# uradmonitor_D.net
KiCad netlist of a schematic drawn in EAGLE
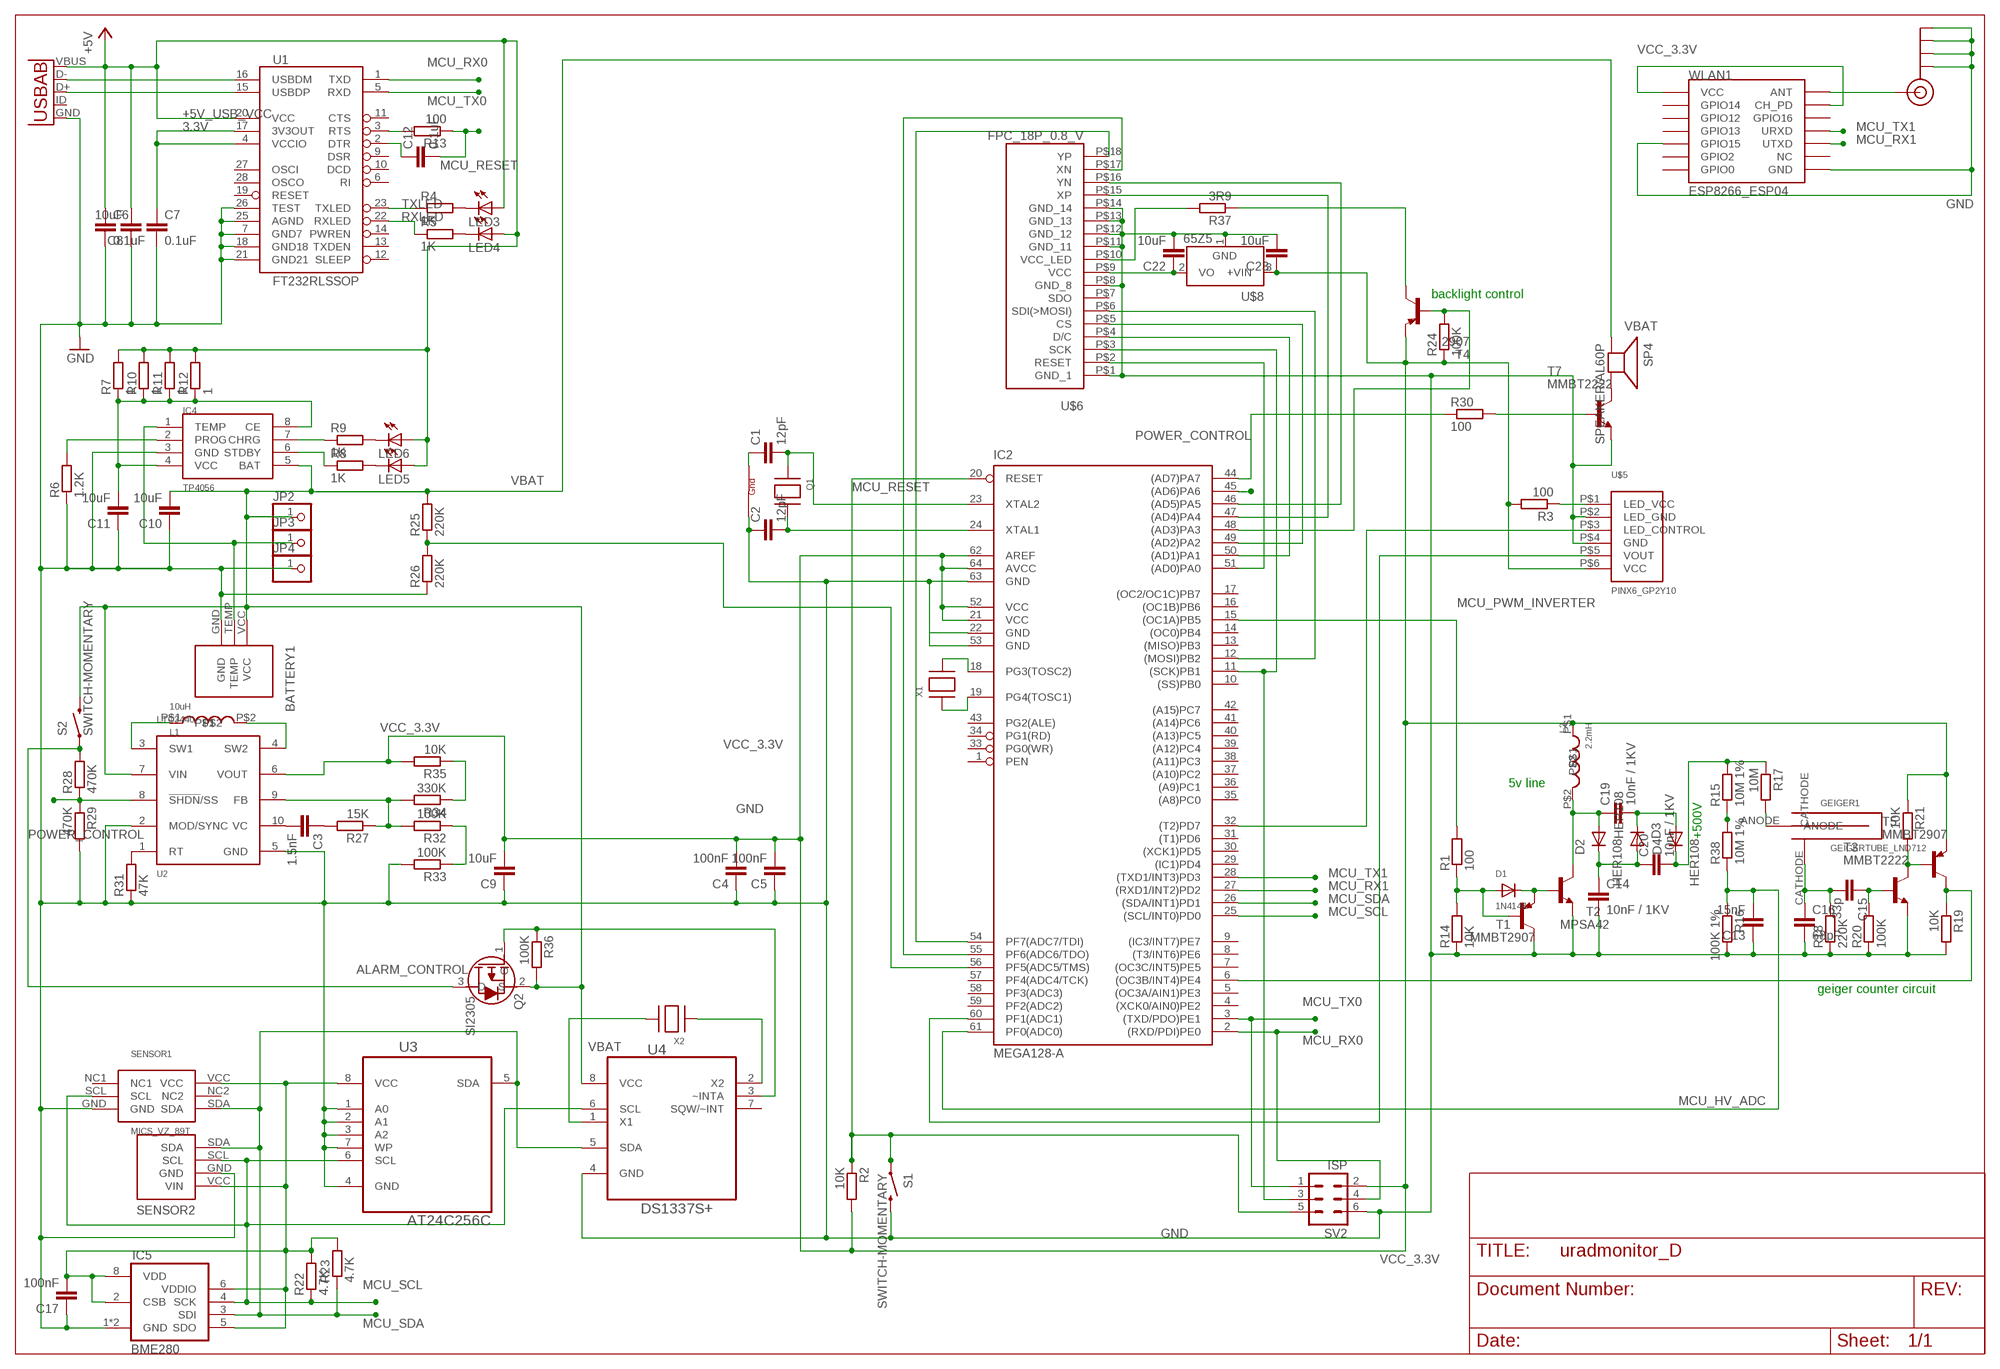
[diagram p0: schematic, sheet 1]

(export (version "E")
  (design (tool "Eeschema 10.0.6"))
  (components
    (comp (ref "BATTERY1")
      (value "BAT-CASIO-NP40BATTERY")
      (footprint "eagle-import:BAT-CASIO-NP40")
      (libsource (lib "eagle-import") (part "BAT-CASIO-NP40BATTERY"))
    )
    (comp (ref "C1")
      (value "12pF")
      (footprint "eagle-import:C0805K")
      (libsource (lib "eagle-import") (part "C-EUC0805K"))
    )
    (comp (ref "C2")
      (value "12pF")
      (footprint "eagle-import:C0805K")
      (libsource (lib "eagle-import") (part "C-EUC0805K"))
    )
    (comp (ref "C3")
      (value "1.5nF")
      (footprint "eagle-import:C0805K")
      (libsource (lib "eagle-import") (part "C-EUC0805K"))
    )
    (comp (ref "C4")
      (value "100nF")
      (footprint "eagle-import:C0805K")
      (libsource (lib "eagle-import") (part "C-EUC0805K"))
    )
    (comp (ref "C5")
      (value "100nF")
      (footprint "eagle-import:C0805K")
      (libsource (lib "eagle-import") (part "C-EUC0805K"))
    )
    (comp (ref "C6")
      (value "0.1uF")
      (footprint "eagle-import:0805")
      (libsource (lib "eagle-import") (part "CAP0805"))
    )
    (comp (ref "C7")
      (value "0.1uF")
      (footprint "eagle-import:0805")
      (libsource (lib "eagle-import") (part "CAP0805"))
    )
    (comp (ref "C8")
      (value "10uF")
      (footprint "eagle-import:C0805K")
      (libsource (lib "eagle-import") (part "C-EUC0805K"))
    )
    (comp (ref "C9")
      (value "10uF")
      (footprint "eagle-import:C0805K")
      (libsource (lib "eagle-import") (part "C-EUC0805K"))
    )
    (comp (ref "C10")
      (value "10uF")
      (footprint "eagle-import:C0805K")
      (libsource (lib "eagle-import") (part "C-EUC0805K"))
    )
    (comp (ref "C11")
      (value "10uF")
      (footprint "eagle-import:C0805K")
      (libsource (lib "eagle-import") (part "C-EUC0805K"))
    )
    (comp (ref "C12")
      (value "0.1uF")
      (footprint "eagle-import:0805")
      (libsource (lib "eagle-import") (part "CAP0805"))
    )
    (comp (ref "C13")
      (value "15nF")
      (footprint "eagle-import:C0805K")
      (libsource (lib "eagle-import") (part "C-EUC0805K"))
    )
    (comp (ref "C14")
      (value "10nF / 1KV")
      (footprint "eagle-import:C1206K")
      (libsource (lib "eagle-import") (part "C-EUC1206K"))
    )
    (comp (ref "C15")
      (value "33p")
      (footprint "eagle-import:C0805K")
      (libsource (lib "eagle-import") (part "C-EUC0805K"))
    )
    (comp (ref "C16")
      (value "68pF")
      (footprint "eagle-import:C0805K")
      (libsource (lib "eagle-import") (part "C-EUC0805K"))
    )
    (comp (ref "C17")
      (value "100nF")
      (footprint "eagle-import:C0805K")
      (libsource (lib "eagle-import") (part "C-EUC0805K"))
    )
    (comp (ref "C19")
      (value "10nF / 1KV")
      (footprint "eagle-import:C1206K")
      (libsource (lib "eagle-import") (part "C-EUC1206K"))
    )
    (comp (ref "C20")
      (value "10nF / 1KV")
      (footprint "eagle-import:C1206K")
      (libsource (lib "eagle-import") (part "C-EUC1206K"))
    )
    (comp (ref "C22")
      (value "10uF")
      (footprint "eagle-import:C0805")
      (libsource (lib "eagle-import") (part "resistor_C-EUC0805"))
    )
    (comp (ref "C23")
      (value "10uF")
      (footprint "eagle-import:C0805")
      (libsource (lib "eagle-import") (part "resistor_C-EUC0805"))
    )
    (comp (ref "D1")
      (value "1N4148")
      (footprint "eagle-import:SOD-323F")
      (libsource (lib "eagle-import") (part "DIODESOD-323F"))
    )
    (comp (ref "D2")
      (value "HER108")
      (footprint "eagle-import:DO-214AC")
      (libsource (lib "eagle-import") (part "DIODE-DO-214AC"))
    )
    (comp (ref "D3")
      (value "HER108")
      (footprint "eagle-import:DO-214AC")
      (libsource (lib "eagle-import") (part "DIODE-DO-214AC"))
    )
    (comp (ref "D4")
      (value "HER108")
      (footprint "eagle-import:DO-214AC")
      (libsource (lib "eagle-import") (part "DIODE-DO-214AC"))
    )
    (comp (ref "GEIGER1")
      (value "GEIGERTUBE_LND712")
      (footprint "eagle-import:GEIGERTUBE_LND712")
      (libsource (lib "eagle-import") (part "GEIGERTUBE_LND712"))
    )
    (comp (ref "IC2")
      (value "MEGA128-A")
      (footprint "eagle-import:TQFP64")
      (fields (field (name "MPN") "ATMEGA128-16AU"))
      (libsource (lib "eagle-import") (part "MEGA128-A"))
    )
    (comp (ref "IC4")
      (value "TP4056")
      (footprint "eagle-import:TP4056")
      (libsource (lib "eagle-import") (part "TP4056"))
    )
    (comp (ref "IC5")
      (value "BME280")
      (footprint "eagle-import:BME280")
      (libsource (lib "eagle-import") (part "BME280"))
    )
    (comp (ref "J$1")
      (value "SMA_EDGE")
      (footprint "eagle-import:SMA-EDGE")
      (libsource (lib "eagle-import") (part "SMA_EDGE"))
    )
    (comp (ref "JP2")
      (value "PINHD-1X1CB")
      (footprint "eagle-import:1X01-CLEANBIG")
      (libsource (lib "eagle-import") (part "PINHD-1X1CB"))
    )
    (comp (ref "JP3")
      (value "PINHD-1X1CB")
      (footprint "eagle-import:1X01-CLEANBIG")
      (libsource (lib "eagle-import") (part "PINHD-1X1CB"))
    )
    (comp (ref "JP4")
      (value "PINHD-1X1CB")
      (footprint "eagle-import:1X01-CLEANBIG")
      (libsource (lib "eagle-import") (part "PINHD-1X1CB"))
    )
    (comp (ref "L1")
      (value "10uH")
      (footprint "eagle-import:DO1608")
      (libsource (lib "eagle-import") (part "INDUCTOR"))
    )
    (comp (ref "L2")
      (value "2.2mH")
      (footprint "eagle-import:DO1608")
      (libsource (lib "eagle-import") (part "INDUCTOR"))
    )
    (comp (ref "LED3")
      (value "LEDCHIP-LED0805")
      (footprint "eagle-import:CHIP-LED0805")
      (libsource (lib "eagle-import") (part "LEDCHIP-LED0805"))
    )
    (comp (ref "LED4")
      (value "LEDCHIP-LED0805")
      (footprint "eagle-import:CHIP-LED0805")
      (libsource (lib "eagle-import") (part "LEDCHIP-LED0805"))
    )
    (comp (ref "LED5")
      (value "LED3MM")
      (footprint "eagle-import:LED3MM")
      (libsource (lib "eagle-import") (part "LED3MM"))
    )
    (comp (ref "LED6")
      (value "LED3MM")
      (footprint "eagle-import:LED3MM")
      (libsource (lib "eagle-import") (part "LED3MM"))
    )
    (comp (ref "Q1")
      (value "XTAL-4-3225")
      (footprint "eagle-import:NX3225")
      (libsource (lib "eagle-import") (part "XTAL-4-3225"))
    )
    (comp (ref "Q2")
      (value "SI2305")
      (footprint "eagle-import:SOT23")
      (libsource (lib "eagle-import") (part "SI2305"))
    )
    (comp (ref "R1")
      (value "100")
      (footprint "eagle-import:R0805")
      (libsource (lib "eagle-import") (part "resistor_R-EU_R0805"))
    )
    (comp (ref "R2")
      (value "10K")
      (footprint "eagle-import:R0805")
      (libsource (lib "eagle-import") (part "R-EU_R0805"))
    )
    (comp (ref "R3")
      (value "100")
      (footprint "eagle-import:R0805")
      (libsource (lib "eagle-import") (part "resistor_R-EU_R0805"))
    )
    (comp (ref "R4")
      (value "1K")
      (footprint "eagle-import:R0805")
      (libsource (lib "eagle-import") (part "R-EU_R0805"))
    )
    (comp (ref "R5")
      (value "1K")
      (footprint "eagle-import:R0805")
      (libsource (lib "eagle-import") (part "R-EU_R0805"))
    )
    (comp (ref "R6")
      (value "1.2K")
      (footprint "eagle-import:R0805")
      (libsource (lib "eagle-import") (part "R-EU_R0805"))
    )
    (comp (ref "R7")
      (value "1")
      (footprint "eagle-import:R0805")
      (libsource (lib "eagle-import") (part "R-EU_R0805"))
    )
    (comp (ref "R8")
      (value "1K")
      (footprint "eagle-import:R0805")
      (libsource (lib "eagle-import") (part "R-EU_R0805"))
    )
    (comp (ref "R9")
      (value "1K")
      (footprint "eagle-import:R0805")
      (libsource (lib "eagle-import") (part "R-EU_R0805"))
    )
    (comp (ref "R10")
      (value "1")
      (footprint "eagle-import:R0805")
      (libsource (lib "eagle-import") (part "R-EU_R0805"))
    )
    (comp (ref "R11")
      (value "1")
      (footprint "eagle-import:R0805")
      (libsource (lib "eagle-import") (part "R-EU_R0805"))
    )
    (comp (ref "R12")
      (value "1")
      (footprint "eagle-import:R0805")
      (libsource (lib "eagle-import") (part "R-EU_R0805"))
    )
    (comp (ref "R13")
      (value "100")
      (footprint "eagle-import:R0805")
      (libsource (lib "eagle-import") (part "R-EU_R0805"))
    )
    (comp (ref "R14")
      (value "10K")
      (footprint "eagle-import:R0805")
      (libsource (lib "eagle-import") (part "resistor_R-EU_R0805"))
    )
    (comp (ref "R15")
      (value "10M 1%")
      (footprint "eagle-import:0204_7")
      (libsource (lib "eagle-import") (part "R-EU_0204/7"))
    )
    (comp (ref "R16")
      (value "100K 1%")
      (footprint "eagle-import:R0805")
      (libsource (lib "eagle-import") (part "R-EU_R0805"))
    )
    (comp (ref "R17")
      (value "10M")
      (footprint "eagle-import:0204_7")
      (libsource (lib "eagle-import") (part "R-EU_0204/7"))
    )
    (comp (ref "R18")
      (value "220K")
      (footprint "eagle-import:0204_7")
      (libsource (lib "eagle-import") (part "R-EU_0204/7"))
    )
    (comp (ref "R19")
      (value "10K")
      (footprint "eagle-import:R0805")
      (libsource (lib "eagle-import") (part "R-EU_R0805"))
    )
    (comp (ref "R20")
      (value "100K")
      (footprint "eagle-import:R0805")
      (libsource (lib "eagle-import") (part "R-EU_R0805"))
    )
    (comp (ref "R21")
      (value "10K")
      (footprint "eagle-import:R0805")
      (libsource (lib "eagle-import") (part "R-EU_R0805"))
    )
    (comp (ref "R22")
      (value "4.7K")
      (footprint "eagle-import:R0805")
      (libsource (lib "eagle-import") (part "R-EU_R0805"))
    )
    (comp (ref "R23")
      (value "4.7K")
      (footprint "eagle-import:R0805")
      (libsource (lib "eagle-import") (part "R-EU_R0805"))
    )
    (comp (ref "R24")
      (value "100K")
      (footprint "eagle-import:R0805")
      (libsource (lib "eagle-import") (part "resistor_R-EU_R0805"))
    )
    (comp (ref "R25")
      (value "220K")
      (footprint "eagle-import:R0805")
      (libsource (lib "eagle-import") (part "R-EU_R0805"))
    )
    (comp (ref "R26")
      (value "220K")
      (footprint "eagle-import:R0805")
      (libsource (lib "eagle-import") (part "R-EU_R0805"))
    )
    (comp (ref "R27")
      (value "15K")
      (footprint "eagle-import:R0805")
      (libsource (lib "eagle-import") (part "R-EU_R0805"))
    )
    (comp (ref "R28")
      (value "470K")
      (footprint "eagle-import:R0805")
      (libsource (lib "eagle-import") (part "R-EU_R0805"))
    )
    (comp (ref "R29")
      (value "470K")
      (footprint "eagle-import:R0805")
      (libsource (lib "eagle-import") (part "R-EU_R0805"))
    )
    (comp (ref "R30")
      (value "100")
      (footprint "eagle-import:R0805")
      (libsource (lib "eagle-import") (part "R-EU_R0805"))
    )
    (comp (ref "R31")
      (value "47K")
      (footprint "eagle-import:R0805")
      (libsource (lib "eagle-import") (part "R-EU_R0805"))
    )
    (comp (ref "R32")
      (value "100K")
      (footprint "eagle-import:R0805")
      (libsource (lib "eagle-import") (part "R-EU_R0805"))
    )
    (comp (ref "R33")
      (value "100K")
      (footprint "eagle-import:R0805")
      (libsource (lib "eagle-import") (part "R-EU_R0805"))
    )
    (comp (ref "R34")
      (value "330K")
      (footprint "eagle-import:R0805")
      (libsource (lib "eagle-import") (part "R-EU_R0805"))
    )
    (comp (ref "R35")
      (value "10K")
      (footprint "eagle-import:R0805")
      (libsource (lib "eagle-import") (part "R-EU_R0805"))
    )
    (comp (ref "R36")
      (value "100K")
      (footprint "eagle-import:R0805")
      (libsource (lib "eagle-import") (part "R-EU_R0805"))
    )
    (comp (ref "R37")
      (value "3R9")
      (footprint "eagle-import:R0805")
      (libsource (lib "eagle-import") (part "resistor_R-EU_R0805"))
    )
    (comp (ref "R38")
      (value "10M 1%")
      (footprint "eagle-import:0204_7")
      (libsource (lib "eagle-import") (part "R-EU_0204/7"))
    )
    (comp (ref "S1")
      (value "SWITCH-MOMENTARY")
      (footprint "eagle-import:TACTILE-SWITCH-1101NE")
      (libsource (lib "eagle-import") (part "SWITCH-MOMENTARY-2-SMD-1101NE"))
    )
    (comp (ref "S2")
      (value "SWITCH-MOMENTARY")
      (footprint "eagle-import:TACTILE-PTH-SIDEEZ")
      (libsource (lib "eagle-import") (part "SWITCH-MOMENTARY-2SIDE_EZ"))
    )
    (comp (ref "SENSOR1")
      (value "MICS_VZ_89T")
      (footprint "eagle-import:MICS_VZ_89T")
      (libsource (lib "eagle-import") (part "MICS_VZ_89T"))
    )
    (comp (ref "SENSOR2")
      (value "BMP180")
      (footprint "eagle-import:SENSOR_GY68")
      (libsource (lib "eagle-import") (part "SENSOR_GY68GY-86DIP"))
    )
    (comp (ref "SP4")
      (value "SPEAKER/AL60P")
      (footprint "eagle-import:AL60P")
      (libsource (lib "eagle-import") (part "SPEAKER/AL60P"))
    )
    (comp (ref "SV2")
      (value "ISP")
      (footprint "eagle-import:MA03-2")
      (libsource (lib "eagle-import") (part "MA03-2"))
    )
    (comp (ref "T1")
      (value "MMBT2907")
      (footprint "eagle-import:SOT23-BEC")
      (libsource (lib "eagle-import") (part "-PNP-SOT23-BECMMBT2907ALT1"))
    )
    (comp (ref "T2")
      (value "MPSA42")
      (footprint "eagle-import:SOT23-BEC")
      (libsource (lib "eagle-import") (part "transistor-neu-to92_-NPN-SOT23-BECMMBTA42LT1"))
    )
    (comp (ref "T3")
      (value "MMBT2222")
      (footprint "eagle-import:SOT23-BEC")
      (libsource (lib "eagle-import") (part "transistor-neu-to92_-NPN-SOT23-BECMMBT2222ALT1"))
    )
    (comp (ref "T4")
      (value "2907")
      (footprint "eagle-import:SOT23-BEC")
      (libsource (lib "eagle-import") (part "-PNP-SOT23-BECMMBT2907ALT1"))
    )
    (comp (ref "T5")
      (value "MMBT2907")
      (footprint "eagle-import:SOT23-BEC")
      (libsource (lib "eagle-import") (part "-PNP-SOT23-BECMMBT2907ALT1"))
    )
    (comp (ref "T7")
      (value "MMBT2222")
      (footprint "eagle-import:SOT23-BEC")
      (libsource (lib "eagle-import") (part "-NPN-SOT23-BECMMBT2222ALT1"))
    )
    (comp (ref "U$2")
      (value "USB_AB")
      (footprint "eagle-import:USB-AB-MICRO-SMD")
      (libsource (lib "eagle-import") (part "USB_AB"))
    )
    (comp (ref "U$5")
      (value "PINX6_GP2Y10")
      (footprint "eagle-import:PINX6_GP2Y10")
      (libsource (lib "eagle-import") (part "PINX6_GP2Y10"))
    )
    (comp (ref "U$6")
      (value "FPC_18P_0.8_V")
      (footprint "eagle-import:FPC_18P_0.8_V")
      (libsource (lib "eagle-import") (part "FPC_18P_0.8_V"))
    )
    (comp (ref "U$8")
      (value "65Z5")
      (footprint "eagle-import:SOT23")
      (libsource (lib "eagle-import") (part "65Z5"))
    )
    (comp (ref "U1")
      (value "FT232RLSSOP")
      (footprint "eagle-import:SSOP28DB")
      (libsource (lib "eagle-import") (part "FT232RLSSOP"))
    )
    (comp (ref "U2")
      (value "LTC3440")
      (footprint "eagle-import:MSOP-10")
      (libsource (lib "eagle-import") (part "LTC3440"))
    )
    (comp (ref "U3")
      (value "AT24C256C")
      (footprint "eagle-import:SOIC127P600X175-8N")
      (fields (field (name "MPN") "AT24C512BN-SH25-B"))
      (libsource (lib "eagle-import") (part "AT24C512BN-SH25-B"))
    )
    (comp (ref "U4")
      (value "DS1337S+")
      (footprint "eagle-import:SOIC127P600X175-8N")
      (libsource (lib "eagle-import") (part "DS1337S+"))
    )
    (comp (ref "WLAN1")
      (value "ESP8266_ESP04")
      (footprint "eagle-import:ESP8266_ESP04")
      (libsource (lib "eagle-import") (part "ESP8266_ESP04"))
    )
    (comp (ref "X1")
      (value "XTAL-3.2X1.5")
      (footprint "eagle-import:XTAL3215")
      (libsource (lib "eagle-import") (part "XTAL-3.2X1.5"))
    )
    (comp (ref "X2")
      (value "XTAL-3.2X1.5")
      (footprint "eagle-import:XTAL3215")
      (libsource (lib "eagle-import") (part "XTAL-3.2X1.5"))
    )
  )
  (nets
    (net (code "1") (name "+5V") (class "Default")
      (node (ref "C6") (pin "1") (pinfunction "1_1") (pintype "passive"))
      (node (ref "C8") (pin "2") (pinfunction "2_2") (pintype "passive"))
      (node (ref "LED3") (pin "A") (pinfunction "A_A") (pintype "passive"))
      (node (ref "LED4") (pin "A") (pinfunction "A_A") (pintype "passive"))
      (node (ref "LED5") (pin "A") (pinfunction "A_A") (pintype "passive"))
      (node (ref "LED6") (pin "A") (pinfunction "A_A") (pintype "passive"))
      (node (ref "R10") (pin "2") (pinfunction "2_2") (pintype "passive"))
      (node (ref "R11") (pin "2") (pinfunction "2_2") (pintype "passive"))
      (node (ref "R12") (pin "2") (pinfunction "2_2") (pintype "passive"))
      (node (ref "R7") (pin "2") (pinfunction "2_2") (pintype "passive"))
      (node (ref "U$2") (pin "VBUS") (pinfunction "VBUS_VBUS") (pintype "bidirectional"))
      (node (ref "U1") (pin "20") (pinfunction "VCC_20") (pintype "power_in"))
    )
    (net (code "2") (name "/3.3V") (class "Default")
      (node (ref "C7") (pin "1") (pinfunction "1_1") (pintype "passive"))
      (node (ref "U1") (pin "17") (pinfunction "3V3OUT_17") (pintype "output"))
      (node (ref "U1") (pin "4") (pinfunction "VCCIO_4") (pintype "power_in"))
    )
    (net (code "3") (name "/ALARM_CONTROL") (class "Default")
      (node (ref "Q2") (pin "3") (pinfunction "D_3") (pintype "bidirectional"))
      (node (ref "R28") (pin "2") (pinfunction "2_2") (pintype "passive"))
      (node (ref "S2") (pin "1") (pinfunction "1_1") (pintype "passive"))
    )
    (net (code "4") (name "/MCU_HV_ADC") (class "Default")
      (node (ref "C13") (pin "2") (pinfunction "2_2") (pintype "passive"))
      (node (ref "IC2") (pin "61") (pinfunction "PF0(ADC0)_61") (pintype "input"))
      (node (ref "R16") (pin "1") (pinfunction "1_1") (pintype "passive"))
      (node (ref "R38") (pin "1") (pinfunction "1_1") (pintype "passive"))
    )
    (net (code "5") (name "/MCU_PWM_INVERTER") (class "Default")
      (node (ref "IC2") (pin "15") (pinfunction "(OC1A)PB5_15") (pintype "bidirectional"))
      (node (ref "R1") (pin "2") (pinfunction "2_2") (pintype "passive"))
    )
    (net (code "6") (name "/MCU_RESET") (class "Default")
      (node (ref "C12") (pin "2") (pinfunction "2_2") (pintype "passive"))
      (node (ref "IC2") (pin "20") (pinfunction "RESET_20") (pintype "input"))
      (node (ref "R13") (pin "1") (pinfunction "1_1") (pintype "passive"))
      (node (ref "R2") (pin "1") (pinfunction "1_1") (pintype "passive"))
      (node (ref "S1") (pin "P$1") (pinfunction "1_P$1") (pintype "passive"))
      (node (ref "SV2") (pin "5") (pinfunction "5_5") (pintype "passive"))
    )
    (net (code "7") (name "/MCU_RX0") (class "Default")
      (node (ref "IC2") (pin "2") (pinfunction "(RXD/PDI)PE0_2") (pintype "bidirectional"))
      (node (ref "SV2") (pin "4") (pinfunction "4_4") (pintype "passive"))
      (node (ref "U1") (pin "1") (pinfunction "TXD_1") (pintype "output"))
    )
    (net (code "8") (name "/MCU_RX1") (class "Default")
      (node (ref "IC2") (pin "27") (pinfunction "(RXD1/INT2)PD2_27") (pintype "bidirectional"))
      (node (ref "WLAN1") (pin "UTXD") (pinfunction "UTXD_UTXD") (pintype "bidirectional"))
    )
    (net (code "9") (name "/MCU_SCL") (class "Default")
      (node (ref "IC2") (pin "25") (pinfunction "(SCL/INT0)PD0_25") (pintype "bidirectional"))
      (node (ref "IC5") (pin "4") (pinfunction "SCK_4") (pintype "bidirectional"))
      (node (ref "R22") (pin "1") (pinfunction "1_1") (pintype "passive"))
      (node (ref "SENSOR1") (pin "SCL") (pinfunction "SCL_SCL") (pintype "bidirectional"))
      (node (ref "SENSOR2") (pin "SCL") (pinfunction "SCL_SCL") (pintype "bidirectional"))
      (node (ref "U3") (pin "6") (pinfunction "SCL_6") (pintype "input"))
      (node (ref "U4") (pin "6") (pinfunction "SCL_6") (pintype "input"))
    )
    (net (code "10") (name "/MCU_SDA") (class "Default")
      (node (ref "IC2") (pin "26") (pinfunction "(SDA/INT1)PD1_26") (pintype "bidirectional"))
      (node (ref "IC5") (pin "3") (pinfunction "SDI_3") (pintype "bidirectional"))
      (node (ref "R23") (pin "1") (pinfunction "1_1") (pintype "passive"))
      (node (ref "SENSOR1") (pin "SDA") (pinfunction "SDA_SDA") (pintype "bidirectional"))
      (node (ref "SENSOR2") (pin "SDA") (pinfunction "SDA_SDA") (pintype "bidirectional"))
      (node (ref "U3") (pin "5") (pinfunction "SDA_5") (pintype "bidirectional"))
      (node (ref "U4") (pin "5") (pinfunction "SDA_5") (pintype "bidirectional"))
    )
    (net (code "11") (name "/MCU_TX0") (class "Default")
      (node (ref "IC2") (pin "3") (pinfunction "(TXD/PDO)PE1_3") (pintype "bidirectional"))
      (node (ref "SV2") (pin "1") (pinfunction "1_1") (pintype "passive"))
      (node (ref "U1") (pin "5") (pinfunction "RXD_5") (pintype "input"))
    )
    (net (code "12") (name "/MCU_TX1") (class "Default")
      (node (ref "IC2") (pin "28") (pinfunction "(TXD1/INT3)PD3_28") (pintype "bidirectional"))
      (node (ref "WLAN1") (pin "URXD") (pinfunction "URXD_URXD") (pintype "bidirectional"))
    )
    (net (code "13") (name "/POWER_CONTROL") (class "Default")
      (node (ref "IC2") (pin "45") (pinfunction "(AD6)PA6_45") (pintype "bidirectional"))
      (node (ref "R28") (pin "1") (pinfunction "1_1") (pintype "passive"))
      (node (ref "R29") (pin "1") (pinfunction "1_1") (pintype "passive"))
      (node (ref "U2") (pin "8") (pinfunction "~{SHDN}/SS_8") (pintype "bidirectional"))
    )
    (net (code "14") (name "/RXLED") (class "Default")
      (node (ref "R5") (pin "1") (pinfunction "1_1") (pintype "passive"))
      (node (ref "U1") (pin "22") (pinfunction "RXLED_22") (pintype "input"))
    )
    (net (code "15") (name "/TXLED") (class "Default")
      (node (ref "R4") (pin "1") (pinfunction "1_1") (pintype "passive"))
      (node (ref "U1") (pin "23") (pinfunction "TXLED_23") (pintype "input"))
    )
    (net (code "16") (name "/VBAT") (class "Default")
      (node (ref "BATTERY1") (pin "VCC") (pinfunction "VCC_VCC") (pintype "bidirectional"))
      (node (ref "C10") (pin "2") (pinfunction "2_2") (pintype "passive"))
      (node (ref "IC4") (pin "5") (pinfunction "BAT_5") (pintype "bidirectional"))
      (node (ref "JP2") (pin "1") (pinfunction "1_1") (pintype "passive"))
      (node (ref "Q2") (pin "2") (pinfunction "S_2") (pintype "bidirectional"))
      (node (ref "R25") (pin "2") (pinfunction "2_2") (pintype "passive"))
      (node (ref "R36") (pin "2") (pinfunction "2_2") (pintype "passive"))
      (node (ref "S2") (pin "2") (pinfunction "2_2") (pintype "passive"))
      (node (ref "SP4") (pin "1") (pinfunction "+_1") (pintype "passive"))
      (node (ref "U2") (pin "7") (pinfunction "VIN_7") (pintype "bidirectional"))
      (node (ref "U4") (pin "8") (pinfunction "VCC_8") (pintype "power_in"))
    )
    (net (code "17") (name "/VCC_3.3V") (class "Default")
      (node (ref "C17") (pin "2") (pinfunction "2_2") (pintype "passive"))
      (node (ref "C23") (pin "1") (pinfunction "1_1") (pintype "passive"))
      (node (ref "C4") (pin "2") (pinfunction "2_2") (pintype "passive"))
      (node (ref "C5") (pin "2") (pinfunction "2_2") (pintype "passive"))
      (node (ref "C9") (pin "2") (pinfunction "2_2") (pintype "passive"))
      (node (ref "IC2") (pin "21") (pinfunction "VCC_21") (pintype "power_in"))
      (node (ref "IC2") (pin "52") (pinfunction "VCC_52") (pintype "power_in"))
      (node (ref "IC2") (pin "62") (pinfunction "AREF_62") (pintype "passive"))
      (node (ref "IC2") (pin "64") (pinfunction "AVCC_64") (pintype "power_in"))
      (node (ref "IC5") (pin "2") (pinfunction "CSB_2") (pintype "input"))
      (node (ref "IC5") (pin "5") (pinfunction "SDO_5") (pintype "input"))
      (node (ref "IC5") (pin "6") (pinfunction "VDDIO_6") (pintype "power_in"))
      (node (ref "IC5") (pin "8") (pinfunction "VDD_8") (pintype "power_in"))
      (node (ref "L2") (pin "P$1") (pinfunction "P$1_P$1") (pintype "bidirectional"))
      (node (ref "R2") (pin "2") (pinfunction "2_2") (pintype "passive"))
      (node (ref "R21") (pin "1") (pinfunction "1_1") (pintype "passive"))
      (node (ref "R22") (pin "2") (pinfunction "2_2") (pintype "passive"))
      (node (ref "R23") (pin "2") (pinfunction "2_2") (pintype "passive"))
      (node (ref "R24") (pin "1") (pinfunction "1_1") (pintype "passive"))
      (node (ref "R3") (pin "2") (pinfunction "2_2") (pintype "passive"))
      (node (ref "R35") (pin "2") (pinfunction "2_2") (pintype "passive"))
      (node (ref "SENSOR1") (pin "VCC") (pinfunction "VCC_VCC") (pintype "bidirectional"))
      (node (ref "SENSOR2") (pin "VCC") (pinfunction "VIN_VCC") (pintype "bidirectional"))
      (node (ref "SV2") (pin "2") (pinfunction "2_2") (pintype "passive"))
      (node (ref "T4") (pin "E") (pinfunction "E_E") (pintype "passive"))
      (node (ref "T5") (pin "E") (pinfunction "E_E") (pintype "passive"))
      (node (ref "U$5") (pin "P$6") (pinfunction "VCC_P$6") (pintype "bidirectional"))
      (node (ref "U$8") (pin "3") (pinfunction "+VIN_3") (pintype "input"))
      (node (ref "U2") (pin "6") (pinfunction "VOUT_6") (pintype "bidirectional"))
      (node (ref "U3") (pin "8") (pinfunction "VCC_8") (pintype "power_in"))
      (node (ref "WLAN1") (pin "CH_PD") (pinfunction "CH_PD_CH_PD") (pintype "bidirectional"))
      (node (ref "WLAN1") (pin "VCC") (pinfunction "VCC_VCC") (pintype "bidirectional"))
    )
    (net (code "18") (name "GND") (class "Default")
      (node (ref "BATTERY1") (pin "GND") (pinfunction "GND_GND") (pintype "bidirectional"))
      (node (ref "C10") (pin "1") (pinfunction "1_1") (pintype "passive"))
      (node (ref "C11") (pin "1") (pinfunction "1_1") (pintype "passive"))
      (node (ref "C13") (pin "1") (pinfunction "1_1") (pintype "passive"))
      (node (ref "C14") (pin "2") (pinfunction "2_2") (pintype "passive"))
      (node (ref "C16") (pin "2") (pinfunction "2_2") (pintype "passive"))
      (node (ref "C17") (pin "1") (pinfunction "1_1") (pintype "passive"))
      (node (ref "C2") (pin "1") (pinfunction "1_1") (pintype "passive"))
      (node (ref "C22") (pin "2") (pinfunction "2_2") (pintype "passive"))
      (node (ref "C23") (pin "2") (pinfunction "2_2") (pintype "passive"))
      (node (ref "C4") (pin "1") (pinfunction "1_1") (pintype "passive"))
      (node (ref "C5") (pin "1") (pinfunction "1_1") (pintype "passive"))
      (node (ref "C6") (pin "2") (pinfunction "2_2") (pintype "passive"))
      (node (ref "C7") (pin "2") (pinfunction "2_2") (pintype "passive"))
      (node (ref "C8") (pin "1") (pinfunction "1_1") (pintype "passive"))
      (node (ref "C9") (pin "1") (pinfunction "1_1") (pintype "passive"))
      (node (ref "IC2") (pin "22") (pinfunction "GND_22") (pintype "power_in"))
      (node (ref "IC2") (pin "53") (pinfunction "GND_53") (pintype "power_in"))
      (node (ref "IC2") (pin "63") (pinfunction "GND_63") (pintype "power_in"))
      (node (ref "IC4") (pin "3") (pinfunction "GND_3") (pintype "bidirectional"))
      (node (ref "IC5") (pin "1") (pinfunction "GND_1") (pintype "power_in"))
      (node (ref "IC5") (pin "7") (pinfunction "GND_7") (pintype "power_in"))
      (node (ref "J$1") (pin "GND@0") (pinfunction "GND_GND@0") (pintype "bidirectional"))
      (node (ref "J$1") (pin "GND@1") (pinfunction "GND_GND@1") (pintype "bidirectional"))
      (node (ref "J$1") (pin "GND@2") (pinfunction "GND_GND@2") (pintype "bidirectional"))
      (node (ref "J$1") (pin "GND@3") (pinfunction "GND_GND@3") (pintype "bidirectional"))
      (node (ref "JP4") (pin "1") (pinfunction "1_1") (pintype "passive"))
      (node (ref "Q1") (pin "2") (pinfunction "G2_2") (pintype "power_in"))
      (node (ref "R14") (pin "1") (pinfunction "1_1") (pintype "passive"))
      (node (ref "R16") (pin "2") (pinfunction "2_2") (pintype "passive"))
      (node (ref "R18") (pin "1") (pinfunction "1_1") (pintype "passive"))
      (node (ref "R19") (pin "2") (pinfunction "2_2") (pintype "passive"))
      (node (ref "R20") (pin "1") (pinfunction "1_1") (pintype "passive"))
      (node (ref "R26") (pin "1") (pinfunction "1_1") (pintype "passive"))
      (node (ref "R29") (pin "2") (pinfunction "2_2") (pintype "passive"))
      (node (ref "R31") (pin "1") (pinfunction "1_1") (pintype "passive"))
      (node (ref "R33") (pin "2") (pinfunction "2_2") (pintype "passive"))
      (node (ref "R6") (pin "1") (pinfunction "1_1") (pintype "passive"))
      (node (ref "S1") (pin "P$2") (pinfunction "2_P$2") (pintype "passive"))
      (node (ref "SENSOR1") (pin "GND") (pinfunction "GND_GND") (pintype "bidirectional"))
      (node (ref "SENSOR2") (pin "GND") (pinfunction "GND_GND") (pintype "bidirectional"))
      (node (ref "SV2") (pin "6") (pinfunction "6_6") (pintype "passive"))
      (node (ref "T1") (pin "C") (pinfunction "C_C") (pintype "passive"))
      (node (ref "T2") (pin "E") (pinfunction "E_E") (pintype "passive"))
      (node (ref "T3") (pin "E") (pinfunction "E_E") (pintype "passive"))
      (node (ref "T7") (pin "E") (pinfunction "E_E") (pintype "passive"))
      (node (ref "U$2") (pin "GND") (pinfunction "GND_GND") (pintype "bidirectional"))
      (node (ref "U$5") (pin "P$2") (pinfunction "LED_GND_P$2") (pintype "bidirectional"))
      (node (ref "U$5") (pin "P$4") (pinfunction "GND_P$4") (pintype "bidirectional"))
      (node (ref "U$6") (pin "P$1") (pinfunction "GND_1_P$1") (pintype "bidirectional"))
      (node (ref "U$6") (pin "P$11") (pinfunction "GND_11_P$11") (pintype "bidirectional"))
      (node (ref "U$6") (pin "P$12") (pinfunction "GND_12_P$12") (pintype "bidirectional"))
      (node (ref "U$6") (pin "P$13") (pinfunction "GND_13_P$13") (pintype "bidirectional"))
      (node (ref "U$6") (pin "P$14") (pinfunction "GND_14_P$14") (pintype "bidirectional"))
      (node (ref "U$6") (pin "P$8") (pinfunction "GND_8_P$8") (pintype "bidirectional"))
      (node (ref "U$8") (pin "1") (pinfunction "GND_1") (pintype "power_in"))
      (node (ref "U1") (pin "18") (pinfunction "GND18_18") (pintype "power_in"))
      (node (ref "U1") (pin "21") (pinfunction "GND21_21") (pintype "power_in"))
      (node (ref "U1") (pin "25") (pinfunction "AGND_25") (pintype "power_in"))
      (node (ref "U1") (pin "26") (pinfunction "TEST_26") (pintype "input"))
      (node (ref "U1") (pin "7") (pinfunction "GND7_7") (pintype "power_in"))
      (node (ref "U2") (pin "2") (pinfunction "MOD/SYNC_2") (pintype "bidirectional"))
      (node (ref "U2") (pin "5") (pinfunction "GND_5") (pintype "bidirectional"))
      (node (ref "U3") (pin "1") (pinfunction "A0_1") (pintype "input"))
      (node (ref "U3") (pin "2") (pinfunction "A1_2") (pintype "input"))
      (node (ref "U3") (pin "3") (pinfunction "A2_3") (pintype "input"))
      (node (ref "U3") (pin "4") (pinfunction "GND_4") (pintype "passive"))
      (node (ref "U3") (pin "7") (pinfunction "WP_7") (pintype "input"))
      (node (ref "U4") (pin "4") (pinfunction "GND_4") (pintype "passive"))
      (node (ref "WLAN1") (pin "GND") (pinfunction "GND_GND") (pintype "bidirectional"))
      (node (ref "WLAN1") (pin "GPIO15") (pinfunction "GPIO15_GPIO15") (pintype "bidirectional"))
    )
    (net (code "19") (name "Net-(C3-Pad1)") (class "Default")
      (node (ref "C3") (pin "1") (pinfunction "1_1") (pintype "passive"))
      (node (ref "R27") (pin "2") (pinfunction "2_2") (pintype "passive"))
    )
    (net (code "20") (name "Net-(C14-Pad1)") (class "Default")
      (node (ref "C14") (pin "1") (pinfunction "1_1") (pintype "passive"))
      (node (ref "C20") (pin "1") (pinfunction "1_1") (pintype "passive"))
      (node (ref "D2") (pin "C") (pinfunction "C_C") (pintype "passive"))
      (node (ref "D3") (pin "A") (pinfunction "A_A") (pintype "passive"))
    )
    (net (code "21") (name "Net-(C15-Pad1)") (class "Default")
      (node (ref "C15") (pin "1") (pinfunction "1_1") (pintype "passive"))
      (node (ref "R20") (pin "2") (pinfunction "2_2") (pintype "passive"))
      (node (ref "T3") (pin "B") (pinfunction "B_B") (pintype "passive"))
    )
    (net (code "22") (name "Net-(C15-Pad2)") (class "Default")
      (node (ref "C15") (pin "2") (pinfunction "2_2") (pintype "passive"))
      (node (ref "C16") (pin "1") (pinfunction "1_1") (pintype "passive"))
      (node (ref "GEIGER1") (pin "CATHODE") (pinfunction "CATHODE_CATHODE") (pintype "bidirectional"))
      (node (ref "R18") (pin "2") (pinfunction "2_2") (pintype "passive"))
    )
    (net (code "23") (name "Net-(C19-Pad1)") (class "Default")
      (node (ref "C19") (pin "1") (pinfunction "1_1") (pintype "passive"))
      (node (ref "D2") (pin "A") (pinfunction "A_A") (pintype "passive"))
      (node (ref "L2") (pin "P$2") (pinfunction "P$2_P$2") (pintype "bidirectional"))
      (node (ref "T2") (pin "C") (pinfunction "C_C") (pintype "passive"))
    )
    (net (code "24") (name "Net-(C19-Pad2)") (class "Default")
      (node (ref "C19") (pin "2") (pinfunction "2_2") (pintype "passive"))
      (node (ref "D3") (pin "C") (pinfunction "C_C") (pintype "passive"))
      (node (ref "D4") (pin "A") (pinfunction "A_A") (pintype "passive"))
    )
    (net (code "25") (name "Net-(C20-Pad2)") (class "Default")
      (node (ref "C20") (pin "2") (pinfunction "2_2") (pintype "passive"))
      (node (ref "D4") (pin "C") (pinfunction "C_C") (pintype "passive"))
      (node (ref "R15") (pin "2") (pinfunction "2_2") (pintype "passive"))
      (node (ref "R17") (pin "1") (pinfunction "1_1") (pintype "passive"))
    )
    (net (code "26") (name "Net-(D1-PadA)") (class "Default")
      (node (ref "D1") (pin "A") (pinfunction "A_A") (pintype "passive"))
      (node (ref "R1") (pin "1") (pinfunction "1_1") (pintype "passive"))
      (node (ref "R14") (pin "2") (pinfunction "2_2") (pintype "passive"))
      (node (ref "T1") (pin "B") (pinfunction "B_B") (pintype "passive"))
    )
    (net (code "27") (name "Net-(D1-PadC)") (class "Default")
      (node (ref "D1") (pin "C") (pinfunction "C_C") (pintype "passive"))
      (node (ref "T1") (pin "E") (pinfunction "E_E") (pintype "passive"))
      (node (ref "T2") (pin "B") (pinfunction "B_B") (pintype "passive"))
    )
    (net (code "28") (name "Net-(GEIGER1-PadANODE)") (class "Default")
      (node (ref "GEIGER1") (pin "ANODE") (pinfunction "ANODE_ANODE") (pintype "bidirectional"))
      (node (ref "R17") (pin "2") (pinfunction "2_2") (pintype "passive"))
    )
    (net (code "29") (name "Net-(IC2-(AD0)PA0)") (class "Default")
      (node (ref "IC2") (pin "51") (pinfunction "(AD0)PA0_51") (pintype "bidirectional"))
      (node (ref "U$6") (pin "P$2") (pinfunction "RESET_P$2") (pintype "bidirectional"))
    )
    (net (code "30") (name "Net-(IC2-(AD1)PA1)") (class "Default")
      (node (ref "IC2") (pin "50") (pinfunction "(AD1)PA1_50") (pintype "bidirectional"))
      (node (ref "U$6") (pin "P$4") (pinfunction "D/C_P$4") (pintype "bidirectional"))
    )
    (net (code "31") (name "Net-(IC2-(AD2)PA2)") (class "Default")
      (node (ref "IC2") (pin "49") (pinfunction "(AD2)PA2_49") (pintype "bidirectional"))
      (node (ref "U$6") (pin "P$5") (pinfunction "CS_P$5") (pintype "bidirectional"))
    )
    (net (code "32") (name "Net-(IC2-(AD3)PA3)") (class "Default")
      (node (ref "IC2") (pin "48") (pinfunction "(AD3)PA3_48") (pintype "bidirectional"))
      (node (ref "R24") (pin "2") (pinfunction "2_2") (pintype "passive"))
      (node (ref "T4") (pin "B") (pinfunction "B_B") (pintype "passive"))
    )
    (net (code "33") (name "Net-(IC2-(AD4)PA4)") (class "Default")
      (node (ref "IC2") (pin "47") (pinfunction "(AD4)PA4_47") (pintype "bidirectional"))
      (node (ref "U$6") (pin "P$15") (pinfunction "XP_P$15") (pintype "bidirectional"))
    )
    (net (code "34") (name "Net-(IC2-(AD5)PA5)") (class "Default")
      (node (ref "IC2") (pin "46") (pinfunction "(AD5)PA5_46") (pintype "bidirectional"))
      (node (ref "U$6") (pin "P$16") (pinfunction "YN_P$16") (pintype "bidirectional"))
    )
    (net (code "35") (name "Net-(IC2-(AD7)PA7)") (class "Default")
      (node (ref "IC2") (pin "44") (pinfunction "(AD7)PA7_44") (pintype "bidirectional"))
      (node (ref "R30") (pin "1") (pinfunction "1_1") (pintype "passive"))
    )
    (net (code "36") (name "Net-(IC2-(MOSI)PB2)") (class "Default")
      (node (ref "IC2") (pin "12") (pinfunction "(MOSI)PB2_12") (pintype "bidirectional"))
      (node (ref "U$6") (pin "P$6") (pinfunction "SDI(>MOSI)_P$6") (pintype "bidirectional"))
    )
    (net (code "37") (name "Net-(IC2-(OC3B{slash}INT4)PE4)") (class "Default")
      (node (ref "IC2") (pin "6") (pinfunction "(OC3B/INT4)PE4_6") (pintype "bidirectional"))
      (node (ref "R19") (pin "1") (pinfunction "1_1") (pintype "passive"))
      (node (ref "T5") (pin "C") (pinfunction "C_C") (pintype "passive"))
    )
    (net (code "38") (name "Net-(IC2-(SCK)PB1)") (class "Default")
      (node (ref "IC2") (pin "11") (pinfunction "(SCK)PB1_11") (pintype "bidirectional"))
      (node (ref "SV2") (pin "3") (pinfunction "3_3") (pintype "passive"))
      (node (ref "U$6") (pin "P$3") (pinfunction "SCK_P$3") (pintype "bidirectional"))
    )
    (net (code "39") (name "Net-(IC2-(T2)PD7)") (class "Default")
      (node (ref "IC2") (pin "32") (pinfunction "(T2)PD7_32") (pintype "bidirectional"))
      (node (ref "U$5") (pin "P$3") (pinfunction "LED_CONTROL_P$3") (pintype "bidirectional"))
    )
    (net (code "40") (name "Net-(IC2-PF1(ADC1))") (class "Default")
      (node (ref "IC2") (pin "60") (pinfunction "PF1(ADC1)_60") (pintype "input"))
      (node (ref "U$5") (pin "P$5") (pinfunction "VOUT_P$5") (pintype "bidirectional"))
    )
    (net (code "41") (name "Net-(IC2-PF5(ADC5{slash}TMS))") (class "Default")
      (node (ref "IC2") (pin "56") (pinfunction "PF5(ADC5/TMS)_56") (pintype "input"))
      (node (ref "R25") (pin "1") (pinfunction "1_1") (pintype "passive"))
      (node (ref "R26") (pin "2") (pinfunction "2_2") (pintype "passive"))
    )
    (net (code "42") (name "Net-(IC2-PF6(ADC6{slash}TDO))") (class "Default")
      (node (ref "IC2") (pin "55") (pinfunction "PF6(ADC6/TDO)_55") (pintype "input"))
      (node (ref "U$6") (pin "P$17") (pinfunction "XN_P$17") (pintype "bidirectional"))
    )
    (net (code "43") (name "Net-(IC2-PF7(ADC7{slash}TDI))") (class "Default")
      (node (ref "IC2") (pin "54") (pinfunction "PF7(ADC7/TDI)_54") (pintype "input"))
      (node (ref "U$6") (pin "P$18") (pinfunction "YP_P$18") (pintype "bidirectional"))
    )
    (net (code "44") (name "Net-(IC2-PG3(TOSC2))") (class "Default")
      (node (ref "IC2") (pin "18") (pinfunction "PG3(TOSC2)_18") (pintype "bidirectional"))
      (node (ref "X1") (pin "P$2") (pinfunction "P$2_P$2") (pintype "bidirectional"))
    )
    (net (code "45") (name "Net-(IC2-PG4(TOSC1))") (class "Default")
      (node (ref "IC2") (pin "19") (pinfunction "PG4(TOSC1)_19") (pintype "bidirectional"))
      (node (ref "X1") (pin "P$1") (pinfunction "P$1_P$1") (pintype "bidirectional"))
    )
    (net (code "46") (name "Net-(IC2-XTAL1)") (class "Default")
      (node (ref "C2") (pin "2") (pinfunction "2_2") (pintype "passive"))
      (node (ref "IC2") (pin "24") (pinfunction "XTAL1_24") (pintype "bidirectional"))
      (node (ref "Q1") (pin "3") (pinfunction "X2_3") (pintype "bidirectional"))
    )
    (net (code "47") (name "Net-(IC2-XTAL2)") (class "Default")
      (node (ref "C1") (pin "2") (pinfunction "2_2") (pintype "passive"))
      (node (ref "IC2") (pin "23") (pinfunction "XTAL2_23") (pintype "bidirectional"))
      (node (ref "Q1") (pin "1") (pinfunction "X1_1") (pintype "bidirectional"))
    )
    (net (code "48") (name "Net-(IC4-CE)") (class "Default")
      (node (ref "C11") (pin "2") (pinfunction "2_2") (pintype "passive"))
      (node (ref "IC4") (pin "4") (pinfunction "VCC_4") (pintype "bidirectional"))
      (node (ref "IC4") (pin "8") (pinfunction "CE_8") (pintype "bidirectional"))
      (node (ref "R10") (pin "1") (pinfunction "1_1") (pintype "passive"))
      (node (ref "R11") (pin "1") (pinfunction "1_1") (pintype "passive"))
      (node (ref "R12") (pin "1") (pinfunction "1_1") (pintype "passive"))
      (node (ref "R7") (pin "1") (pinfunction "1_1") (pintype "passive"))
    )
    (net (code "49") (name "Net-(IC4-CHRG)") (class "Default")
      (node (ref "IC4") (pin "7") (pinfunction "CHRG_7") (pintype "bidirectional"))
      (node (ref "R9") (pin "1") (pinfunction "1_1") (pintype "passive"))
    )
    (net (code "50") (name "Net-(IC4-PROG)") (class "Default")
      (node (ref "IC4") (pin "2") (pinfunction "PROG_2") (pintype "bidirectional"))
      (node (ref "R6") (pin "2") (pinfunction "2_2") (pintype "passive"))
    )
    (net (code "51") (name "Net-(IC4-STDBY)") (class "Default")
      (node (ref "IC4") (pin "6") (pinfunction "STDBY_6") (pintype "bidirectional"))
      (node (ref "R8") (pin "1") (pinfunction "1_1") (pintype "passive"))
    )
    (net (code "52") (name "Net-(IC4-TEMP)") (class "Default")
      (node (ref "BATTERY1") (pin "TEMP") (pinfunction "TEMP_TEMP") (pintype "bidirectional"))
      (node (ref "IC4") (pin "1") (pinfunction "TEMP_1") (pintype "bidirectional"))
      (node (ref "JP3") (pin "1") (pinfunction "1_1") (pintype "passive"))
    )
    (net (code "53") (name "Net-(J$1-SIGNAL)") (class "Default")
      (node (ref "J$1") (pin "SIG") (pinfunction "SIGNAL_SIG") (pintype "bidirectional"))
      (node (ref "WLAN1") (pin "ANT") (pinfunction "ANT_ANT") (pintype "bidirectional"))
    )
    (net (code "54") (name "Net-(LED3-PadC)") (class "Default")
      (node (ref "LED3") (pin "C") (pinfunction "C_C") (pintype "passive"))
      (node (ref "R4") (pin "2") (pinfunction "2_2") (pintype "passive"))
    )
    (net (code "55") (name "Net-(LED4-PadC)") (class "Default")
      (node (ref "LED4") (pin "C") (pinfunction "C_C") (pintype "passive"))
      (node (ref "R5") (pin "2") (pinfunction "2_2") (pintype "passive"))
    )
    (net (code "56") (name "Net-(LED5-C)") (class "Default")
      (node (ref "LED5") (pin "K") (pinfunction "C_K") (pintype "passive"))
      (node (ref "R8") (pin "2") (pinfunction "2_2") (pintype "passive"))
    )
    (net (code "57") (name "Net-(LED6-C)") (class "Default")
      (node (ref "LED6") (pin "K") (pinfunction "C_K") (pintype "passive"))
      (node (ref "R9") (pin "2") (pinfunction "2_2") (pintype "passive"))
    )
    (net (code "58") (name "Net-(Q1-G1)") (class "Default")
      (node (ref "C1") (pin "1") (pinfunction "1_1") (pintype "passive"))
      (node (ref "Q1") (pin "4") (pinfunction "G1_4") (pintype "power_in"))
    )
    (net (code "59") (name "Net-(Q2-G)") (class "Default")
      (node (ref "Q2") (pin "1") (pinfunction "G_1") (pintype "bidirectional"))
      (node (ref "R36") (pin "1") (pinfunction "1_1") (pintype "passive"))
      (node (ref "U4") (pin "3") (pinfunction "~{INTA}_3") (pintype "output"))
    )
    (net (code "60") (name "Net-(R15-Pad1)") (class "Default")
      (node (ref "R15") (pin "1") (pinfunction "1_1") (pintype "passive"))
      (node (ref "R38") (pin "2") (pinfunction "2_2") (pintype "passive"))
    )
    (net (code "61") (name "Net-(R21-Pad2)") (class "Default")
      (node (ref "R21") (pin "2") (pinfunction "2_2") (pintype "passive"))
      (node (ref "T3") (pin "C") (pinfunction "C_C") (pintype "passive"))
      (node (ref "T5") (pin "B") (pinfunction "B_B") (pintype "passive"))
    )
    (net (code "62") (name "Net-(R30-Pad2)") (class "Default")
      (node (ref "R30") (pin "2") (pinfunction "2_2") (pintype "passive"))
      (node (ref "T7") (pin "B") (pinfunction "B_B") (pintype "passive"))
    )
    (net (code "63") (name "Net-(R32-Pad1)") (class "Default")
      (node (ref "R32") (pin "1") (pinfunction "1_1") (pintype "passive"))
      (node (ref "R33") (pin "1") (pinfunction "1_1") (pintype "passive"))
    )
    (net (code "64") (name "Net-(R34-Pad1)") (class "Default")
      (node (ref "R34") (pin "1") (pinfunction "1_1") (pintype "passive"))
      (node (ref "R35") (pin "1") (pinfunction "1_1") (pintype "passive"))
    )
    (net (code "65") (name "Net-(R37-Pad1)") (class "Default")
      (node (ref "R37") (pin "1") (pinfunction "1_1") (pintype "passive"))
      (node (ref "T4") (pin "C") (pinfunction "C_C") (pintype "passive"))
    )
    (net (code "66") (name "Net-(SP4--)") (class "Default")
      (node (ref "SP4") (pin "2") (pinfunction "-_2") (pintype "passive"))
      (node (ref "T7") (pin "C") (pinfunction "C_C") (pintype "passive"))
    )
    (net (code "67") (name "Net-(U$5-LED_VCC)") (class "Default")
      (node (ref "R3") (pin "1") (pinfunction "1_1") (pintype "passive"))
      (node (ref "U$5") (pin "P$1") (pinfunction "LED_VCC_P$1") (pintype "bidirectional"))
    )
    (net (code "68") (name "Net-(U$6-VCC)") (class "Default")
      (node (ref "C22") (pin "1") (pinfunction "1_1") (pintype "passive"))
      (node (ref "U$6") (pin "P$9") (pinfunction "VCC_P$9") (pintype "bidirectional"))
      (node (ref "U$8") (pin "2") (pinfunction "VO_2") (pintype "input"))
    )
    (net (code "69") (name "Net-(U$6-VCC_LED)") (class "Default")
      (node (ref "R37") (pin "2") (pinfunction "2_2") (pintype "passive"))
      (node (ref "U$6") (pin "P$10") (pinfunction "VCC_LED_P$10") (pintype "bidirectional"))
    )
    (net (code "70") (name "Net-(U1-DTR)") (class "Default")
      (node (ref "C12") (pin "1") (pinfunction "1_1") (pintype "passive"))
      (node (ref "U1") (pin "2") (pinfunction "DTR_2") (pintype "output"))
    )
    (net (code "71") (name "Net-(U1-RTS)") (class "Default")
      (node (ref "R13") (pin "2") (pinfunction "2_2") (pintype "passive"))
      (node (ref "U1") (pin "3") (pinfunction "RTS_3") (pintype "output"))
    )
    (net (code "72") (name "Net-(U1-USBDM)") (class "Default")
      (node (ref "U$2") (pin "D-") (pinfunction "D-_D-") (pintype "bidirectional"))
      (node (ref "U1") (pin "16") (pinfunction "USBDM_16") (pintype "bidirectional"))
    )
    (net (code "73") (name "Net-(U1-USBDP)") (class "Default")
      (node (ref "U$2") (pin "D+") (pinfunction "D+_D+") (pintype "bidirectional"))
      (node (ref "U1") (pin "15") (pinfunction "USBDP_15") (pintype "bidirectional"))
    )
    (net (code "74") (name "Net-(U2-FB)") (class "Default")
      (node (ref "R27") (pin "1") (pinfunction "1_1") (pintype "passive"))
      (node (ref "R32") (pin "2") (pinfunction "2_2") (pintype "passive"))
      (node (ref "R34") (pin "2") (pinfunction "2_2") (pintype "passive"))
      (node (ref "U2") (pin "9") (pinfunction "FB_9") (pintype "bidirectional"))
    )
    (net (code "75") (name "Net-(U2-RT)") (class "Default")
      (node (ref "R31") (pin "2") (pinfunction "2_2") (pintype "passive"))
      (node (ref "U2") (pin "1") (pinfunction "RT_1") (pintype "bidirectional"))
    )
    (net (code "76") (name "Net-(U2-SW1)") (class "Default")
      (node (ref "L1") (pin "P$1") (pinfunction "P$1_P$1") (pintype "bidirectional"))
      (node (ref "U2") (pin "3") (pinfunction "SW1_3") (pintype "bidirectional"))
    )
    (net (code "77") (name "Net-(U2-SW2)") (class "Default")
      (node (ref "L1") (pin "P$2") (pinfunction "P$2_P$2") (pintype "bidirectional"))
      (node (ref "U2") (pin "4") (pinfunction "SW2_4") (pintype "bidirectional"))
    )
    (net (code "78") (name "Net-(U2-VC)") (class "Default")
      (node (ref "C3") (pin "2") (pinfunction "2_2") (pintype "passive"))
      (node (ref "U2") (pin "10") (pinfunction "VC_10") (pintype "bidirectional"))
    )
    (net (code "79") (name "Net-(U4-X1)") (class "Default")
      (node (ref "U4") (pin "1") (pinfunction "X1_1") (pintype "input"))
      (node (ref "X2") (pin "P$2") (pinfunction "P$2_P$2") (pintype "bidirectional"))
    )
    (net (code "80") (name "Net-(U4-X2)") (class "Default")
      (node (ref "U4") (pin "2") (pinfunction "X2_2") (pintype "passive"))
      (node (ref "X2") (pin "P$1") (pinfunction "P$1_P$1") (pintype "bidirectional"))
    )
    (net (code "81") (name "unconnected-(IC2-(A8)PC0-Pad35)") (class "Default")
      (node (ref "IC2") (pin "35") (pinfunction "(A8)PC0_35") (pintype "output"))
    )
    (net (code "82") (name "unconnected-(IC2-(A9)PC1-Pad36)") (class "Default")
      (node (ref "IC2") (pin "36") (pinfunction "(A9)PC1_36") (pintype "output"))
    )
    (net (code "83") (name "unconnected-(IC2-(A10)PC2-Pad37)") (class "Default")
      (node (ref "IC2") (pin "37") (pinfunction "(A10)PC2_37") (pintype "output"))
    )
    (net (code "84") (name "unconnected-(IC2-(A11)PC3-Pad38)") (class "Default")
      (node (ref "IC2") (pin "38") (pinfunction "(A11)PC3_38") (pintype "output"))
    )
    (net (code "85") (name "unconnected-(IC2-(A12)PC4-Pad39)") (class "Default")
      (node (ref "IC2") (pin "39") (pinfunction "(A12)PC4_39") (pintype "output"))
    )
    (net (code "86") (name "unconnected-(IC2-(A13)PC5-Pad40)") (class "Default")
      (node (ref "IC2") (pin "40") (pinfunction "(A13)PC5_40") (pintype "output"))
    )
    (net (code "87") (name "unconnected-(IC2-(A14)PC6-Pad41)") (class "Default")
      (node (ref "IC2") (pin "41") (pinfunction "(A14)PC6_41") (pintype "output"))
    )
    (net (code "88") (name "unconnected-(IC2-(A15)PC7-Pad42)") (class "Default")
      (node (ref "IC2") (pin "42") (pinfunction "(A15)PC7_42") (pintype "output"))
    )
    (net (code "89") (name "unconnected-(IC2-(IC1)PD4-Pad29)") (class "Default")
      (node (ref "IC2") (pin "29") (pinfunction "(IC1)PD4_29") (pintype "bidirectional"))
    )
    (net (code "90") (name "unconnected-(IC2-(IC3{slash}INT7)PE7-Pad9)") (class "Default")
      (node (ref "IC2") (pin "9") (pinfunction "(IC3/INT7)PE7_9") (pintype "bidirectional"))
    )
    (net (code "91") (name "unconnected-(IC2-(MISO)PB3-Pad13)") (class "Default")
      (node (ref "IC2") (pin "13") (pinfunction "(MISO)PB3_13") (pintype "bidirectional"))
    )
    (net (code "92") (name "unconnected-(IC2-(OC0)PB4-Pad14)") (class "Default")
      (node (ref "IC2") (pin "14") (pinfunction "(OC0)PB4_14") (pintype "bidirectional"))
    )
    (net (code "93") (name "unconnected-(IC2-(OC1B)PB6-Pad16)") (class "Default")
      (node (ref "IC2") (pin "16") (pinfunction "(OC1B)PB6_16") (pintype "bidirectional"))
    )
    (net (code "94") (name "unconnected-(IC2-(OC2{slash}OC1C)PB7-Pad17)") (class "Default")
      (node (ref "IC2") (pin "17") (pinfunction "(OC2/OC1C)PB7_17") (pintype "bidirectional"))
    )
    (net (code "95") (name "unconnected-(IC2-(OC3A{slash}AIN1)PE3-Pad5)") (class "Default")
      (node (ref "IC2") (pin "5") (pinfunction "(OC3A/AIN1)PE3_5") (pintype "bidirectional"))
    )
    (net (code "96") (name "unconnected-(IC2-(OC3C{slash}INT5)PE5-Pad7)") (class "Default")
      (node (ref "IC2") (pin "7") (pinfunction "(OC3C/INT5)PE5_7") (pintype "bidirectional"))
    )
    (net (code "97") (name "unconnected-(IC2-(SS)PB0-Pad10)") (class "Default")
      (node (ref "IC2") (pin "10") (pinfunction "(SS)PB0_10") (pintype "bidirectional"))
    )
    (net (code "98") (name "unconnected-(IC2-(T1)PD6-Pad31)") (class "Default")
      (node (ref "IC2") (pin "31") (pinfunction "(T1)PD6_31") (pintype "bidirectional"))
    )
    (net (code "99") (name "unconnected-(IC2-(T3{slash}INT6)PE6-Pad8)") (class "Default")
      (node (ref "IC2") (pin "8") (pinfunction "(T3/INT6)PE6_8") (pintype "bidirectional"))
    )
    (net (code "100") (name "unconnected-(IC2-(XCK0{slash}AIN0)PE2-Pad4)") (class "Default")
      (node (ref "IC2") (pin "4") (pinfunction "(XCK0/AIN0)PE2_4") (pintype "bidirectional"))
    )
    (net (code "101") (name "unconnected-(IC2-(XCK1)PD5-Pad30)") (class "Default")
      (node (ref "IC2") (pin "30") (pinfunction "(XCK1)PD5_30") (pintype "bidirectional"))
    )
    (net (code "102") (name "unconnected-(IC2-PEN-Pad1)") (class "Default")
      (node (ref "IC2") (pin "1") (pinfunction "PEN_1") (pintype "input"))
    )
    (net (code "103") (name "unconnected-(IC2-PF2(ADC2)-Pad59)") (class "Default")
      (node (ref "IC2") (pin "59") (pinfunction "PF2(ADC2)_59") (pintype "input"))
    )
    (net (code "104") (name "unconnected-(IC2-PF3(ADC3)-Pad58)") (class "Default")
      (node (ref "IC2") (pin "58") (pinfunction "PF3(ADC3)_58") (pintype "input"))
    )
    (net (code "105") (name "unconnected-(IC2-PF4(ADC4{slash}TCK)-Pad57)") (class "Default")
      (node (ref "IC2") (pin "57") (pinfunction "PF4(ADC4/TCK)_57") (pintype "input"))
    )
    (net (code "106") (name "unconnected-(IC2-PG0(WR)-Pad33)") (class "Default")
      (node (ref "IC2") (pin "33") (pinfunction "PG0(WR)_33") (pintype "bidirectional"))
    )
    (net (code "107") (name "unconnected-(IC2-PG1(RD)-Pad34)") (class "Default")
      (node (ref "IC2") (pin "34") (pinfunction "PG1(RD)_34") (pintype "bidirectional"))
    )
    (net (code "108") (name "unconnected-(IC2-PG2(ALE)-Pad43)") (class "Default")
      (node (ref "IC2") (pin "43") (pinfunction "PG2(ALE)_43") (pintype "bidirectional"))
    )
    (net (code "109") (name "unconnected-(SENSOR1-PadNC1)") (class "Default")
      (node (ref "SENSOR1") (pin "NC1") (pinfunction "NC1_NC1") (pintype "bidirectional"))
    )
    (net (code "110") (name "unconnected-(SENSOR1-PadNC2)") (class "Default")
      (node (ref "SENSOR1") (pin "NC2") (pinfunction "NC2_NC2") (pintype "bidirectional"))
    )
    (net (code "111") (name "unconnected-(U$2-USBID-PadID)") (class "Default")
      (node (ref "U$2") (pin "ID") (pinfunction "USBID_ID") (pintype "bidirectional"))
    )
    (net (code "112") (name "unconnected-(U$6-SDO-PadP$7)") (class "Default")
      (node (ref "U$6") (pin "P$7") (pinfunction "SDO_P$7") (pintype "bidirectional"))
    )
    (net (code "113") (name "unconnected-(U1-CTS-Pad11)") (class "Default")
      (node (ref "U1") (pin "11") (pinfunction "CTS_11") (pintype "input"))
    )
    (net (code "114") (name "unconnected-(U1-DCD-Pad10)") (class "Default")
      (node (ref "U1") (pin "10") (pinfunction "DCD_10") (pintype "input"))
    )
    (net (code "115") (name "unconnected-(U1-DSR-Pad9)") (class "Default")
      (node (ref "U1") (pin "9") (pinfunction "DSR_9") (pintype "input"))
    )
    (net (code "116") (name "unconnected-(U1-OSCI-Pad27)") (class "Default")
      (node (ref "U1") (pin "27") (pinfunction "OSCI_27") (pintype "input"))
    )
    (net (code "117") (name "unconnected-(U1-OSCO-Pad28)") (class "Default")
      (node (ref "U1") (pin "28") (pinfunction "OSCO_28") (pintype "output"))
    )
    (net (code "118") (name "unconnected-(U1-PWREN-Pad14)") (class "Default")
      (node (ref "U1") (pin "14") (pinfunction "PWREN_14") (pintype "input"))
    )
    (net (code "119") (name "unconnected-(U1-RESET-Pad19)") (class "Default")
      (node (ref "U1") (pin "19") (pinfunction "RESET_19") (pintype "input"))
    )
    (net (code "120") (name "unconnected-(U1-RI-Pad6)") (class "Default")
      (node (ref "U1") (pin "6") (pinfunction "RI_6") (pintype "input"))
    )
    (net (code "121") (name "unconnected-(U1-SLEEP-Pad12)") (class "Default")
      (node (ref "U1") (pin "12") (pinfunction "SLEEP_12") (pintype "input"))
    )
    (net (code "122") (name "unconnected-(U1-TXDEN-Pad13)") (class "Default")
      (node (ref "U1") (pin "13") (pinfunction "TXDEN_13") (pintype "input"))
    )
    (net (code "123") (name "unconnected-(U4-SQW{slash}~{INT}-Pad7)") (class "Default")
      (node (ref "U4") (pin "7") (pinfunction "SQW/~{INT}_7") (pintype "output"))
    )
    (net (code "124") (name "unconnected-(WLAN1-PadGPIO0)") (class "Default")
      (node (ref "WLAN1") (pin "GPIO0") (pinfunction "GPIO0_GPIO0") (pintype "bidirectional"))
    )
    (net (code "125") (name "unconnected-(WLAN1-PadGPIO2)") (class "Default")
      (node (ref "WLAN1") (pin "GPIO2") (pinfunction "GPIO2_GPIO2") (pintype "bidirectional"))
    )
    (net (code "126") (name "unconnected-(WLAN1-PadGPIO12)") (class "Default")
      (node (ref "WLAN1") (pin "GPIO12") (pinfunction "GPIO12_GPIO12") (pintype "bidirectional"))
    )
    (net (code "127") (name "unconnected-(WLAN1-PadGPIO13)") (class "Default")
      (node (ref "WLAN1") (pin "GPIO13") (pinfunction "GPIO13_GPIO13") (pintype "bidirectional"))
    )
    (net (code "128") (name "unconnected-(WLAN1-PadGPIO14)") (class "Default")
      (node (ref "WLAN1") (pin "GPIO14") (pinfunction "GPIO14_GPIO14") (pintype "bidirectional"))
    )
    (net (code "129") (name "unconnected-(WLAN1-PadGPIO16)") (class "Default")
      (node (ref "WLAN1") (pin "GPIO16") (pinfunction "GPIO16_GPIO16") (pintype "bidirectional"))
    )
    (net (code "130") (name "unconnected-(WLAN1-PadNC)") (class "Default")
      (node (ref "WLAN1") (pin "NC") (pinfunction "NC_NC") (pintype "bidirectional"))
    )
  )
)
